# Differential_Noise_Generator.net
KiCad netlist of a schematic drawn in Altium Designer
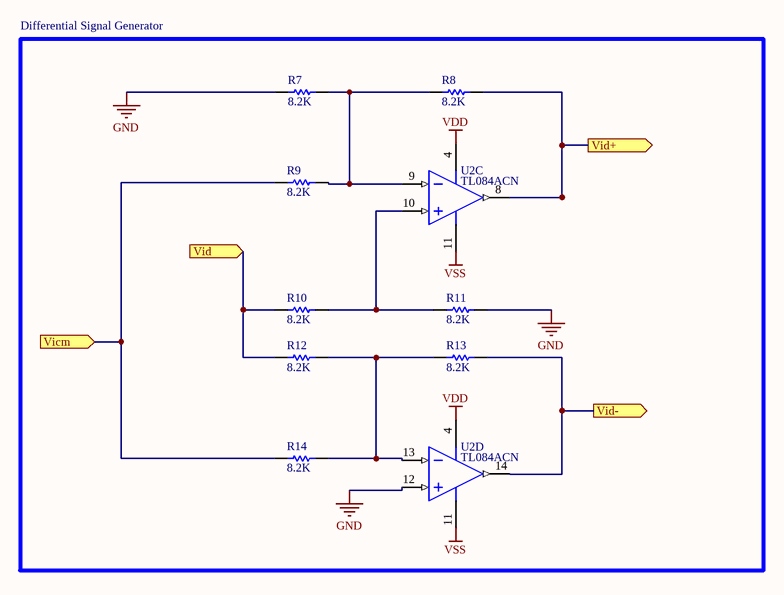
[diagram p0: Differential_Noise_Generator.SchDoc]

(export (version "E")
  (design (tool "Eeschema 10.0.6"))
  (components
    (comp (ref "R7")
      (value "8.2K")
      (footprint "Resistor_Axial 0.4")
      (description "Resistor")
      (fields (field (name "Comment") "Res1") (field (name "PUBLISHER") "Altium Limited"))
      (libsource (lib "signal-generator") (part "Res1"))
    )
    (comp (ref "R8")
      (value "8.2K")
      (footprint "Resistor_Axial 0.4")
      (description "Resistor")
      (fields (field (name "Comment") "Res1") (field (name "PUBLISHER") "Altium Limited"))
      (libsource (lib "signal-generator") (part "Res1"))
    )
    (comp (ref "R9")
      (value "8.2K")
      (footprint "Resistor_Axial 0.4")
      (description "Resistor")
      (fields (field (name "Comment") "Res1") (field (name "PUBLISHER") "Altium Limited"))
      (libsource (lib "signal-generator") (part "Res1"))
    )
    (comp (ref "R10")
      (value "8.2K")
      (footprint "Resistor_Axial 0.4")
      (description "Resistor")
      (fields (field (name "Comment") "Res1") (field (name "PUBLISHER") "Altium Limited"))
      (libsource (lib "signal-generator") (part "Res1"))
    )
    (comp (ref "R11")
      (value "8.2K")
      (footprint "Resistor_Axial 0.4")
      (description "Resistor")
      (fields (field (name "Comment") "Res1") (field (name "PUBLISHER") "Altium Limited"))
      (libsource (lib "signal-generator") (part "Res1"))
    )
    (comp (ref "R12")
      (value "8.2K")
      (footprint "Resistor_Axial 0.4")
      (description "Resistor")
      (fields (field (name "Comment") "Res1") (field (name "PUBLISHER") "Altium Limited"))
      (libsource (lib "signal-generator") (part "Res1"))
    )
    (comp (ref "R13")
      (value "8.2K")
      (footprint "Resistor_Axial 0.4")
      (description "Resistor")
      (fields (field (name "Comment") "Res1") (field (name "PUBLISHER") "Altium Limited"))
      (libsource (lib "signal-generator") (part "Res1"))
    )
    (comp (ref "R14")
      (value "8.2K")
      (footprint "Resistor_Axial 0.4")
      (description "Resistor")
      (fields (field (name "Comment") "Res1") (field (name "PUBLISHER") "Altium Limited"))
      (libsource (lib "signal-generator") (part "Res1"))
    )
    (comp (ref "U2")
      (value "TL084ACN")
      (footprint "N0014A")
      (description "JFET-Input Operational Amplifier, 7 to 36 V, 0 to 70 degC, 14-pin DIP (N14), Pb-Free (RoHS)")
      (fields (field (name "MANUFACTURER") "Texas Instruments"))
      (libsource (lib "Altium Content Vault") (part "TI-TLXX4X_MC3403-X14"))
    )
  )
  (nets
    (net (code "1") (name "/Vicm") (class "Default")
      (node (ref "R14") (pin "1") (pinfunction "1_1") (pintype "passive"))
      (node (ref "R9") (pin "1") (pinfunction "1_1") (pintype "passive"))
    )
    (net (code "2") (name "/Vid") (class "Default")
      (node (ref "R10") (pin "1") (pinfunction "1_1") (pintype "passive"))
      (node (ref "R12") (pin "1") (pinfunction "1_1") (pintype "passive"))
    )
    (net (code "3") (name "/Vid+") (class "Default")
      (node (ref "R8") (pin "2") (pinfunction "2_2") (pintype "passive"))
      (node (ref "U2") (pin "8") (pinfunction "OUT3_8") (pintype "output"))
    )
    (net (code "4") (name "/Vid-") (class "Default")
      (node (ref "R13") (pin "2") (pinfunction "2_2") (pintype "passive"))
      (node (ref "U2") (pin "14") (pinfunction "OUT4_14") (pintype "output"))
    )
    (net (code "5") (name "GND") (class "Default")
      (node (ref "R11") (pin "2") (pinfunction "2_2") (pintype "passive"))
      (node (ref "R7") (pin "1") (pinfunction "1_1") (pintype "passive"))
      (node (ref "U2") (pin "12") (pinfunction "IN4+_12") (pintype "input"))
    )
    (net (code "6") (name "Net-(U2C-IN3+)") (class "Default")
      (node (ref "R10") (pin "2") (pinfunction "2_2") (pintype "passive"))
      (node (ref "R11") (pin "1") (pinfunction "1_1") (pintype "passive"))
      (node (ref "U2") (pin "10") (pinfunction "IN3+_10") (pintype "input"))
    )
    (net (code "7") (name "Net-(U2C-IN3-)") (class "Default")
      (node (ref "R7") (pin "2") (pinfunction "2_2") (pintype "passive"))
      (node (ref "R8") (pin "1") (pinfunction "1_1") (pintype "passive"))
      (node (ref "R9") (pin "2") (pinfunction "2_2") (pintype "passive"))
      (node (ref "U2") (pin "9") (pinfunction "IN3-_9") (pintype "input"))
    )
    (net (code "8") (name "Net-(U2D-IN4-)") (class "Default")
      (node (ref "R12") (pin "2") (pinfunction "2_2") (pintype "passive"))
      (node (ref "R13") (pin "1") (pinfunction "1_1") (pintype "passive"))
      (node (ref "R14") (pin "2") (pinfunction "2_2") (pintype "passive"))
      (node (ref "U2") (pin "13") (pinfunction "IN4-_13") (pintype "input"))
    )
    (net (code "9") (name "VDD") (class "Default")
      (node (ref "U2") (pin "4") (pinfunction "VCC+_4") (pintype "power_in"))
    )
    (net (code "10") (name "VSS") (class "Default")
      (node (ref "U2") (pin "11") (pinfunction "VCC-_11") (pintype "power_in"))
    )
  )
)
